# Motor-E.net
KiCad netlist of a schematic drawn in Altium Designer
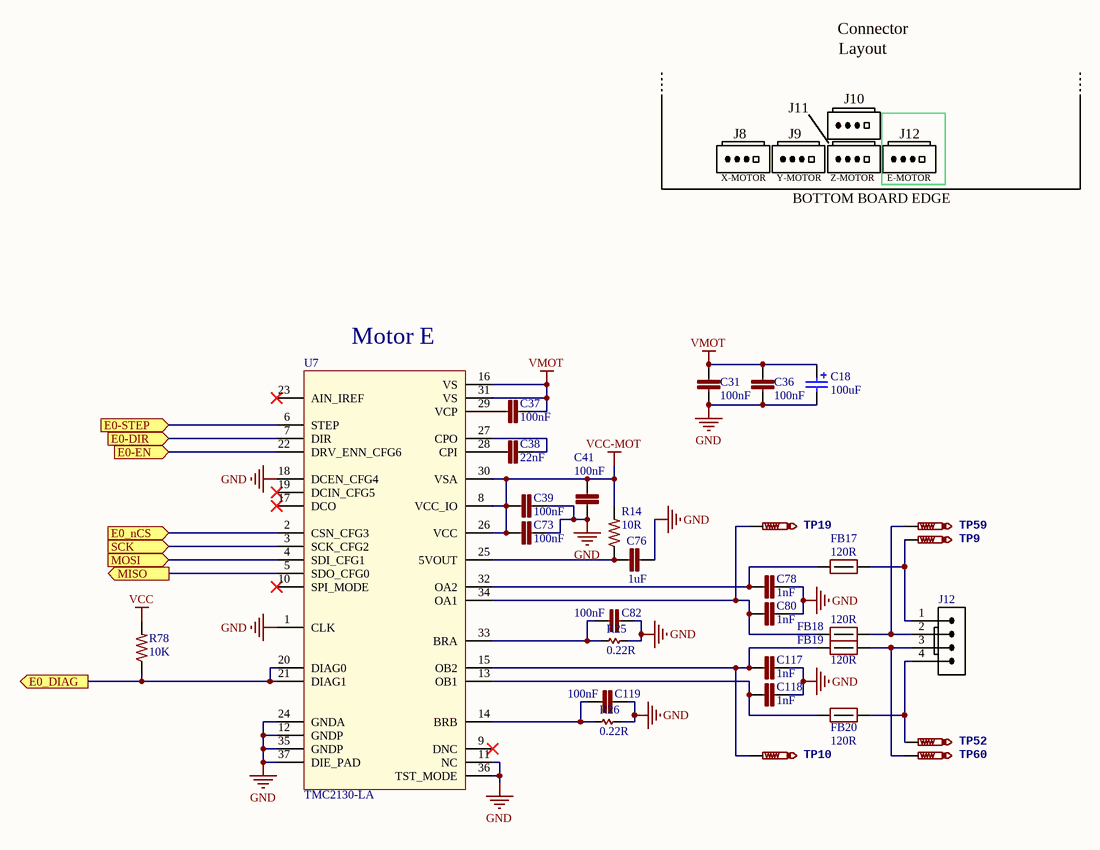
[diagram p0: Motor-E.SchDoc]

(export (version "E")
  (design (tool "Eeschema 10.0.6"))
  (components
    (comp (ref "C18")
      (value "100uF")
      (footprint "CAP-ELEC-063063077")
      (description "CAP ALUM 100UF 35V 20% SMD")
      (fields (field (name "MANUFACTURER") "Nichicon") (field (name "TOLERANCE") "+/- 20%"))
      (libsource (lib "3Delight") (part "UWT1V101MCL1GS"))
    )
    (comp (ref "C31")
      (value "100nF")
      (footprint "C0603")
      (description "CAP CER 0603 100nF 50V 10% X7R")
      (fields (field (name "MANUFACTURER") "Kemet") (field (name "TOLERANCE") "+/- 10%"))
      (libsource (lib "") (part "C0603C104K5RACTU_2"))
    )
    (comp (ref "C36")
      (value "100nF")
      (footprint "C0603")
      (description "CAP CER 0603 100nF 50V 10% X7R")
      (fields (field (name "MANUFACTURER") "Kemet") (field (name "TOLERANCE") "+/- 10%"))
      (libsource (lib "") (part "C0603C104K5RACTU_2"))
    )
    (comp (ref "C37")
      (value "100nF")
      (footprint "C0603")
      (description "CAP CER 0603 100nF 50V 10% X7R")
      (fields (field (name "MANUFACTURER") "Kemet") (field (name "TOLERANCE") "+/- 10%"))
      (libsource (lib "3Delight") (part "C0603C104K5RACTU"))
    )
    (comp (ref "C38")
      (value "22nF")
      (footprint "C0402")
      (description "CAP CER 0402 22nF ±10% 50V X7R")
      (fields (field (name "MANUFACTURER") "YAGEO") (field (name "TOLERANCE") "+/- 10%"))
      (libsource (lib "3Delight") (part "GCM155R71H223KA55D"))
    )
    (comp (ref "C39")
      (value "100nF")
      (footprint "C0402")
      (description "CAP CER 0402 100nF 16V 10% X7R")
      (fields (field (name "MANUFACTURER") "Murata") (field (name "TOLERANCE") "+/- 10%"))
      (libsource (lib "3Delight") (part "GRM155R71C104KA88D"))
    )
    (comp (ref "C41")
      (value "100nF")
      (footprint "C0402")
      (description "CAP CER 0402 100nF 16V 10% X7R")
      (fields (field (name "MANUFACTURER") "Murata") (field (name "TOLERANCE") "+/- 10%"))
      (libsource (lib "") (part "GRM155R71C104KA88D_1"))
    )
    (comp (ref "C73")
      (value "100nF")
      (footprint "C0402")
      (description "CAP CER 0402 100nF 16V 10% X7R")
      (fields (field (name "MANUFACTURER") "Murata") (field (name "TOLERANCE") "+/- 10%"))
      (libsource (lib "3Delight") (part "GRM155R71C104KA88D"))
    )
    (comp (ref "C76")
      (value "1uF")
      (footprint "C0402")
      (description "CAP CER 0402 1uF 6.3V 10% X5R")
      (fields (field (name "MANUFACTURER") "Murata") (field (name "TOLERANCE") "+/- 10%"))
      (libsource (lib "3Delight") (part "GRM155R60J105KE19D"))
    )
    (comp (ref "C78")
      (value "1nF")
      (footprint "C0603")
      (description "CAP CER 0603  1nF 50v 10% X7R")
      (fields (field (name "MANUFACTURER") "Kemet") (field (name "TOLERANCE") "+/- 10%"))
      (libsource (lib "3Delight") (part "C0603C102K5RACTU"))
    )
    (comp (ref "C80")
      (value "1nF")
      (footprint "C0603")
      (description "CAP CER 0603  1nF 50v 10% X7R")
      (fields (field (name "MANUFACTURER") "Kemet") (field (name "TOLERANCE") "+/- 10%"))
      (libsource (lib "3Delight") (part "C0603C102K5RACTU"))
    )
    (comp (ref "C82")
      (value "100nF")
      (footprint "C0603")
      (description "CAP CER 0603 100nF 50V 10% X7R")
      (fields (field (name "MANUFACTURER") "Kemet") (field (name "TOLERANCE") "+/- 10%"))
      (libsource (lib "") (part "C0603C104K5RACTU_1"))
    )
    (comp (ref "C117")
      (value "1nF")
      (footprint "C0603")
      (description "CAP CER 0603  1nF 50v 10% X7R")
      (fields (field (name "MANUFACTURER") "Kemet") (field (name "TOLERANCE") "+/- 10%"))
      (libsource (lib "3Delight") (part "C0603C102K5RACTU"))
    )
    (comp (ref "C118")
      (value "1nF")
      (footprint "C0603")
      (description "CAP CER 0603  1nF 50v 10% X7R")
      (fields (field (name "MANUFACTURER") "Kemet") (field (name "TOLERANCE") "+/- 10%"))
      (libsource (lib "3Delight") (part "C0603C102K5RACTU"))
    )
    (comp (ref "C119")
      (value "100nF")
      (footprint "C0603")
      (description "CAP CER 0603 100nF 50V 10% X7R")
      (fields (field (name "MANUFACTURER") "Kemet") (field (name "TOLERANCE") "+/- 10%"))
      (libsource (lib "") (part "C0603C104K5RACTU_1"))
    )
    (comp (ref "FB17")
      (value "120R")
      (footprint "FB0603")
      (description "FERRITE BEAD 120 OHM 0603 1LN")
      (fields (field (name "MANUFACTURER") "Samsung") (field (name "PART") "FERRITE 120R 3A 0603"))
      (libsource (lib "Inductors") (part "FERRITE 120R 3A 0603"))
    )
    (comp (ref "FB18")
      (value "120R")
      (footprint "FB0603")
      (description "FERRITE BEAD 120 OHM 0603 1LN")
      (fields (field (name "MANUFACTURER") "Samsung") (field (name "PART") "FERRITE 120R 3A 0603"))
      (libsource (lib "Inductors") (part "FERRITE 120R 3A 0603"))
    )
    (comp (ref "FB19")
      (value "120R")
      (footprint "FB0603")
      (description "FERRITE BEAD 120 OHM 0603 1LN")
      (fields (field (name "MANUFACTURER") "Samsung") (field (name "PART") "FERRITE 120R 3A 0603"))
      (libsource (lib "Inductors") (part "FERRITE 120R 3A 0603"))
    )
    (comp (ref "FB20")
      (value "120R")
      (footprint "FB0603")
      (description "FERRITE BEAD 120 OHM 0603 1LN")
      (fields (field (name "MANUFACTURER") "Samsung") (field (name "PART") "FERRITE 120R 3A 0603"))
      (libsource (lib "Inductors") (part "FERRITE 120R 3A 0603"))
    )
    (comp (ref "J12")
      (value "Molex 0705430003")
      (footprint "4POL254")
      (description "Molex 4 Pin Clip Connector")
      (fields (field (name "MANUFACTURER") "Molex") (field (name "PART") "4 Pin Conn"))
      (libsource (lib "3Delight") (part "CONN 4PIN 0.1{dblquote} VERT SHRD LOCK ALT"))
    )
    (comp (ref "R14")
      (value "10R")
      (footprint "R0402")
      (description "RES SMD 10 OHM 1% 1/16W 0402")
      (fields (field (name "MANUFACTURER") "Yageo") (field (name "TOLERANCE") "+/- 1%"))
      (libsource (lib "3Delight") (part "RC0402FR-0710RL"))
    )
    (comp (ref "R25")
      (value "0.22R")
      (footprint "R1206")
      (description "RES SMD 0.22 OHM 1% 1/3W 1206")
      (fields (field (name "MANUFACTURER") "Panasonic") (field (name "TOLERANCE") "+/- 1%"))
      (libsource (lib "Resistors") (part "0.22R 1% 1206"))
    )
    (comp (ref "R26")
      (value "0.22R")
      (footprint "R1206")
      (description "RES SMD 0.22 OHM 1% 1/3W 1206")
      (fields (field (name "MANUFACTURER") "Panasonic") (field (name "TOLERANCE") "+/- 1%"))
      (libsource (lib "Resistors") (part "0.22R 1% 1206"))
    )
    (comp (ref "R78")
      (value "10K")
      (footprint "R0402")
      (description "RES SMD 10K OHM 1% 1/16W 0402")
      (fields (field (name "MANUFACTURER") "Yageo") (field (name "PART") "10k 1% 0402"))
      (libsource (lib "3Delight") (part "RC0402FR-0710KP"))
    )
    (comp (ref "TP9")
      (value "TestPoint")
      (footprint "TP1-27")
      (description "Test Point")
      (libsource (lib "3Delight") (part "TestPoint"))
    )
    (comp (ref "TP10")
      (value "TestPoint")
      (footprint "TP1-27")
      (description "Test Point")
      (libsource (lib "3Delight") (part "TestPoint"))
    )
    (comp (ref "TP19")
      (value "TestPoint")
      (footprint "TP1-27")
      (description "Test Point")
      (libsource (lib "3Delight") (part "TestPoint"))
    )
    (comp (ref "TP52")
      (value "TestPoint")
      (footprint "TP1-27")
      (description "Test Point")
      (libsource (lib "3Delight") (part "TestPoint"))
    )
    (comp (ref "TP59")
      (value "TestPoint")
      (footprint "TP1-27")
      (description "Test Point")
      (libsource (lib "3Delight") (part "TestPoint"))
    )
    (comp (ref "TP60")
      (value "TestPoint")
      (footprint "TP1-27")
      (description "Test Point")
      (libsource (lib "3Delight") (part "TestPoint"))
    )
    (comp (ref "U7")
      (value "TMC2130-LA")
      (footprint "QFN36-50P500X600X900_HS-37N")
      (description "IC STEPPER MOTOR DVR SPI 36QFN")
      (fields (field (name "MANUFACTURER") "Trinamic") (field (name "PART") "TMC2130"))
      (libsource (lib "3Delight") (part "TMC2130-LA-T"))
    )
  )
  (nets
    (net (code "1") (name "/E0-DIR") (class "Default")
      (node (ref "U7") (pin "7") (pinfunction "DIR_7") (pintype "passive"))
    )
    (net (code "2") (name "/E0-EN") (class "Default")
      (node (ref "U7") (pin "22") (pinfunction "DRV_ENN_CFG6_22") (pintype "passive"))
    )
    (net (code "3") (name "/E0-STEP") (class "Default")
      (node (ref "U7") (pin "6") (pinfunction "STEP_6") (pintype "passive"))
    )
    (net (code "4") (name "/E0_DIAG") (class "Default")
      (node (ref "R78") (pin "1") (pinfunction "1_1") (pintype "passive"))
      (node (ref "U7") (pin "20") (pinfunction "DIAG0_20") (pintype "passive"))
      (node (ref "U7") (pin "21") (pinfunction "DIAG1_21") (pintype "passive"))
    )
    (net (code "5") (name "/E0_nCS") (class "Default")
      (node (ref "U7") (pin "2") (pinfunction "CSN_CFG3_2") (pintype "passive"))
    )
    (net (code "6") (name "/MISO") (class "Default")
      (node (ref "U7") (pin "5") (pinfunction "SDO_CFG0_5") (pintype "passive"))
    )
    (net (code "7") (name "/MOSI") (class "Default")
      (node (ref "U7") (pin "4") (pinfunction "SDI_CFG1_4") (pintype "passive"))
    )
    (net (code "8") (name "/SCK") (class "Default")
      (node (ref "U7") (pin "3") (pinfunction "SCK_CFG2_3") (pintype "passive"))
    )
    (net (code "9") (name "GND") (class "Default")
      (node (ref "C117") (pin "2") (pinfunction "2_2") (pintype "passive"))
      (node (ref "C118") (pin "2") (pinfunction "2_2") (pintype "passive"))
      (node (ref "C119") (pin "1") (pinfunction "1_1") (pintype "passive"))
      (node (ref "C18") (pin "2") (pinfunction "2_2") (pintype "passive"))
      (node (ref "C31") (pin "1") (pinfunction "1_1") (pintype "passive"))
      (node (ref "C36") (pin "1") (pinfunction "1_1") (pintype "passive"))
      (node (ref "C39") (pin "1") (pinfunction "1_1") (pintype "passive"))
      (node (ref "C41") (pin "1") (pinfunction "1_1") (pintype "passive"))
      (node (ref "C73") (pin "1") (pinfunction "1_1") (pintype "passive"))
      (node (ref "C76") (pin "2") (pinfunction "2_2") (pintype "passive"))
      (node (ref "C78") (pin "2") (pinfunction "2_2") (pintype "passive"))
      (node (ref "C80") (pin "2") (pinfunction "2_2") (pintype "passive"))
      (node (ref "C82") (pin "1") (pinfunction "1_1") (pintype "passive"))
      (node (ref "R25") (pin "2") (pinfunction "2_2") (pintype "passive"))
      (node (ref "R26") (pin "2") (pinfunction "2_2") (pintype "passive"))
      (node (ref "U7") (pin "1") (pinfunction "CLK_1") (pintype "passive"))
      (node (ref "U7") (pin "11") (pinfunction "NC_11") (pintype "passive"))
      (node (ref "U7") (pin "12") (pinfunction "GNDP_12") (pintype "passive"))
      (node (ref "U7") (pin "18") (pinfunction "DCEN_CFG4_18") (pintype "passive"))
      (node (ref "U7") (pin "24") (pinfunction "GNDA_24") (pintype "passive"))
      (node (ref "U7") (pin "35") (pinfunction "GNDP_35") (pintype "passive"))
      (node (ref "U7") (pin "36") (pinfunction "TST_MODE_36") (pintype "passive"))
      (node (ref "U7") (pin "37") (pinfunction "DIE_PAD_37") (pintype "passive"))
    )
    (net (code "10") (name "Net-(FB17-Pad2)") (class "Default")
      (node (ref "FB17") (pin "2") (pinfunction "2_2") (pintype "passive"))
      (node (ref "J12") (pin "1") (pinfunction "1_1") (pintype "passive"))
      (node (ref "TP9") (pin "TP") (pinfunction "TP_TP") (pintype "passive"))
    )
    (net (code "11") (name "Net-(FB18-Pad2)") (class "Default")
      (node (ref "FB18") (pin "2") (pinfunction "2_2") (pintype "passive"))
      (node (ref "J12") (pin "2") (pinfunction "2_2") (pintype "passive"))
      (node (ref "TP59") (pin "TP") (pinfunction "TP_TP") (pintype "passive"))
    )
    (net (code "12") (name "Net-(FB19-Pad2)") (class "Default")
      (node (ref "FB19") (pin "2") (pinfunction "2_2") (pintype "passive"))
      (node (ref "J12") (pin "3") (pinfunction "3_3") (pintype "passive"))
      (node (ref "TP60") (pin "TP") (pinfunction "TP_TP") (pintype "passive"))
    )
    (net (code "13") (name "Net-(FB20-Pad2)") (class "Default")
      (node (ref "FB20") (pin "2") (pinfunction "2_2") (pintype "passive"))
      (node (ref "J12") (pin "4") (pinfunction "4_4") (pintype "passive"))
      (node (ref "TP52") (pin "TP") (pinfunction "TP_TP") (pintype "passive"))
    )
    (net (code "14") (name "Net-(U7-5VOUT)") (class "Default")
      (node (ref "C76") (pin "1") (pinfunction "1_1") (pintype "passive"))
      (node (ref "R14") (pin "1") (pinfunction "1_1") (pintype "passive"))
      (node (ref "U7") (pin "25") (pinfunction "5VOUT_25") (pintype "passive"))
    )
    (net (code "15") (name "Net-(U7-BRA)") (class "Default")
      (node (ref "C82") (pin "2") (pinfunction "2_2") (pintype "passive"))
      (node (ref "R25") (pin "1") (pinfunction "1_1") (pintype "passive"))
      (node (ref "U7") (pin "33") (pinfunction "BRA_33") (pintype "passive"))
    )
    (net (code "16") (name "Net-(U7-BRB)") (class "Default")
      (node (ref "C119") (pin "2") (pinfunction "2_2") (pintype "passive"))
      (node (ref "R26") (pin "1") (pinfunction "1_1") (pintype "passive"))
      (node (ref "U7") (pin "14") (pinfunction "BRB_14") (pintype "passive"))
    )
    (net (code "17") (name "Net-(U7-CPI)") (class "Default")
      (node (ref "C38") (pin "1") (pinfunction "1_1") (pintype "passive"))
      (node (ref "U7") (pin "28") (pinfunction "CPI_28") (pintype "passive"))
    )
    (net (code "18") (name "Net-(U7-CPO)") (class "Default")
      (node (ref "C38") (pin "2") (pinfunction "2_2") (pintype "passive"))
      (node (ref "U7") (pin "27") (pinfunction "CPO_27") (pintype "passive"))
    )
    (net (code "19") (name "Net-(U7-OA1)") (class "Default")
      (node (ref "C80") (pin "1") (pinfunction "1_1") (pintype "passive"))
      (node (ref "FB18") (pin "1") (pinfunction "1_1") (pintype "passive"))
      (node (ref "TP19") (pin "TP") (pinfunction "TP_TP") (pintype "passive"))
      (node (ref "U7") (pin "34") (pinfunction "OA1_34") (pintype "passive"))
    )
    (net (code "20") (name "Net-(U7-OA2)") (class "Default")
      (node (ref "C78") (pin "1") (pinfunction "1_1") (pintype "passive"))
      (node (ref "FB17") (pin "1") (pinfunction "1_1") (pintype "passive"))
      (node (ref "U7") (pin "32") (pinfunction "OA2_32") (pintype "passive"))
    )
    (net (code "21") (name "Net-(U7-OB1)") (class "Default")
      (node (ref "C118") (pin "1") (pinfunction "1_1") (pintype "passive"))
      (node (ref "FB20") (pin "1") (pinfunction "1_1") (pintype "passive"))
      (node (ref "U7") (pin "13") (pinfunction "OB1_13") (pintype "passive"))
    )
    (net (code "22") (name "Net-(U7-OB2)") (class "Default")
      (node (ref "C117") (pin "1") (pinfunction "1_1") (pintype "passive"))
      (node (ref "FB19") (pin "1") (pinfunction "1_1") (pintype "passive"))
      (node (ref "TP10") (pin "TP") (pinfunction "TP_TP") (pintype "passive"))
      (node (ref "U7") (pin "15") (pinfunction "OB2_15") (pintype "passive"))
    )
    (net (code "23") (name "Net-(U7-VCP)") (class "Default")
      (node (ref "C37") (pin "1") (pinfunction "1_1") (pintype "passive"))
      (node (ref "U7") (pin "29") (pinfunction "VCP_29") (pintype "passive"))
    )
    (net (code "24") (name "VCC") (class "Default")
      (node (ref "R78") (pin "2") (pinfunction "2_2") (pintype "passive"))
    )
    (net (code "25") (name "VCC-MOT") (class "Default")
      (node (ref "C39") (pin "2") (pinfunction "2_2") (pintype "passive"))
      (node (ref "C41") (pin "2") (pinfunction "2_2") (pintype "passive"))
      (node (ref "C73") (pin "2") (pinfunction "2_2") (pintype "passive"))
      (node (ref "R14") (pin "2") (pinfunction "2_2") (pintype "passive"))
      (node (ref "U7") (pin "26") (pinfunction "VCC_26") (pintype "passive"))
      (node (ref "U7") (pin "30") (pinfunction "VSA_30") (pintype "passive"))
      (node (ref "U7") (pin "8") (pinfunction "VCC_IO_8") (pintype "passive"))
    )
    (net (code "26") (name "VMOT") (class "Default")
      (node (ref "C18") (pin "1") (pinfunction "1_1") (pintype "passive"))
      (node (ref "C31") (pin "2") (pinfunction "2_2") (pintype "passive"))
      (node (ref "C36") (pin "2") (pinfunction "2_2") (pintype "passive"))
      (node (ref "C37") (pin "2") (pinfunction "2_2") (pintype "passive"))
      (node (ref "U7") (pin "16") (pinfunction "VS_16") (pintype "passive"))
      (node (ref "U7") (pin "31") (pinfunction "VS_31") (pintype "passive"))
    )
    (net (code "27") (name "unconnected-(U7-AIN_IREF-Pad23)") (class "Default")
      (node (ref "U7") (pin "23") (pinfunction "AIN_IREF_23") (pintype "passive+no_connect"))
    )
    (net (code "28") (name "unconnected-(U7-DCIN_CFG5-Pad19)") (class "Default")
      (node (ref "U7") (pin "19") (pinfunction "DCIN_CFG5_19") (pintype "passive+no_connect"))
    )
    (net (code "29") (name "unconnected-(U7-DCO-Pad17)") (class "Default")
      (node (ref "U7") (pin "17") (pinfunction "DCO_17") (pintype "passive+no_connect"))
    )
    (net (code "30") (name "unconnected-(U7-DNC-Pad9)") (class "Default")
      (node (ref "U7") (pin "9") (pinfunction "DNC_9") (pintype "passive+no_connect"))
    )
    (net (code "31") (name "unconnected-(U7-SPI_MODE-Pad10)") (class "Default")
      (node (ref "U7") (pin "10") (pinfunction "SPI_MODE_10") (pintype "passive+no_connect"))
    )
  )
)
